# Relay_schematic.net
KiCad netlist of a schematic drawn in Altium Designer
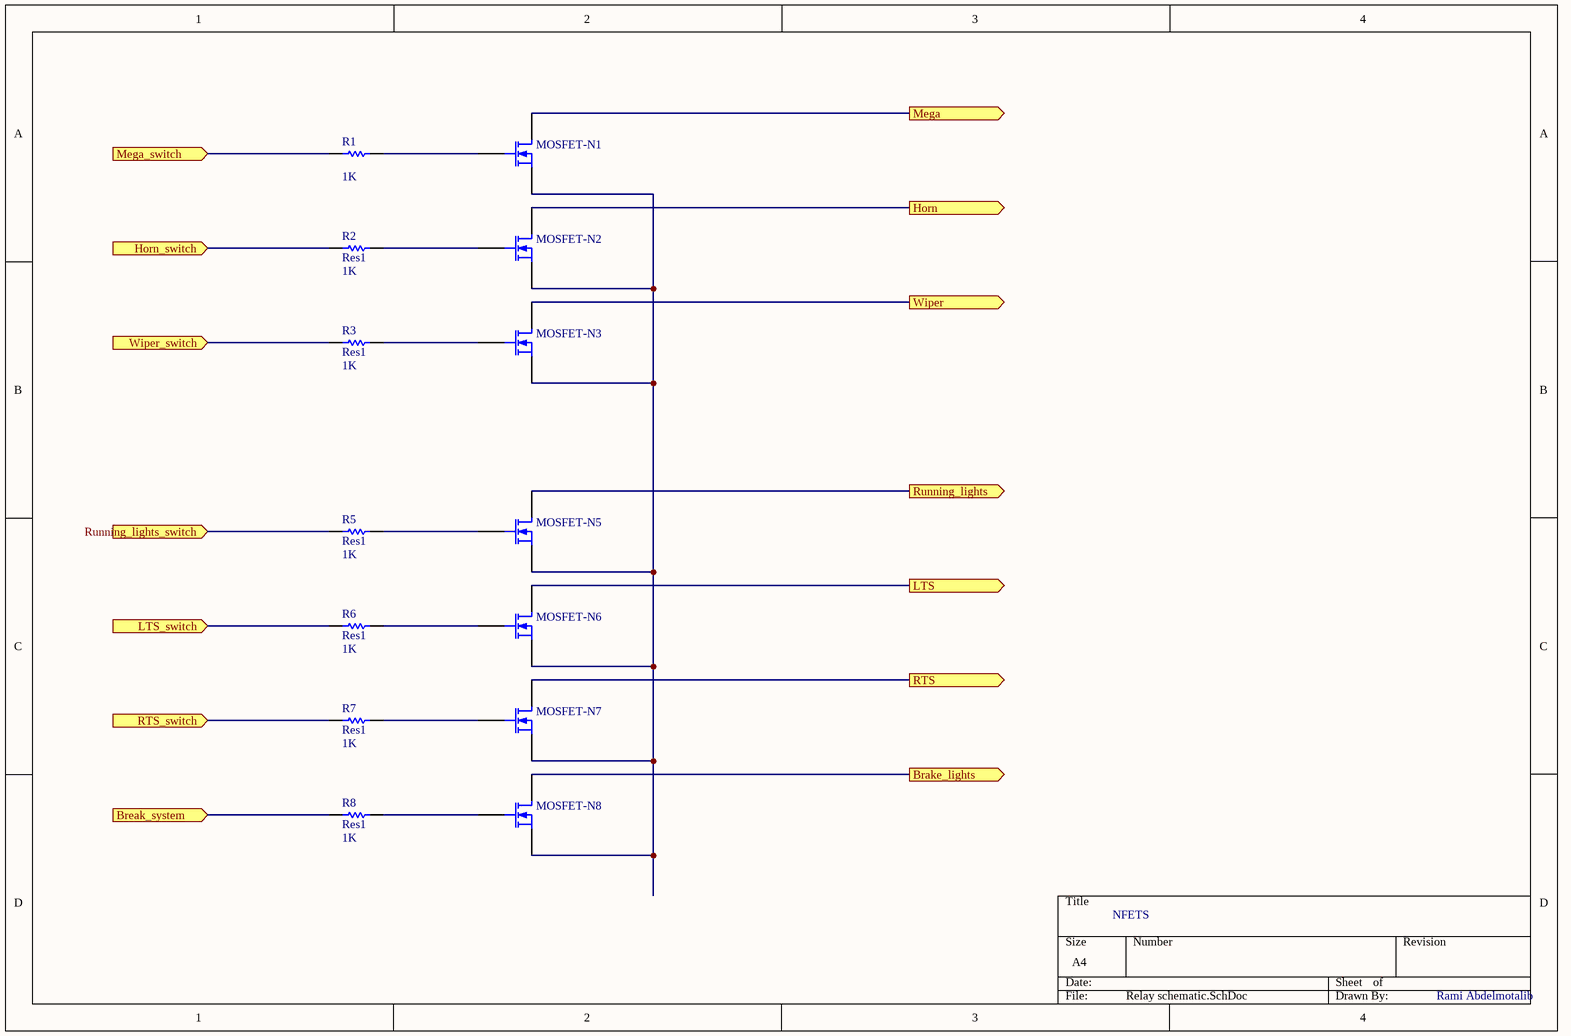
[diagram p0: Relay schematic.SchDoc]

(export (version "E")
  (design (tool "Eeschema 10.0.6"))
  (components
    (comp (ref "MOSFET-N1")
      (value "~")
      (footprint "E3")
      (description "N-Channel MOSFET")
      (fields (field (name "PUBLISHER") "Altium Limited"))
      (libsource (lib "Miscellaneous Devices") (part "MOSFET-N"))
    )
    (comp (ref "MOSFET-N2")
      (value "~")
      (footprint "E3")
      (description "N-Channel MOSFET")
      (fields (field (name "PUBLISHER") "Altium Limited"))
      (libsource (lib "Miscellaneous Devices") (part "MOSFET-N"))
    )
    (comp (ref "MOSFET-N3")
      (value "~")
      (footprint "E3")
      (description "N-Channel MOSFET")
      (fields (field (name "PUBLISHER") "Altium Limited"))
      (libsource (lib "Miscellaneous Devices") (part "MOSFET-N"))
    )
    (comp (ref "MOSFET-N5")
      (value "~")
      (footprint "E3")
      (description "N-Channel MOSFET")
      (fields (field (name "PUBLISHER") "Altium Limited"))
      (libsource (lib "Miscellaneous Devices") (part "MOSFET-N"))
    )
    (comp (ref "MOSFET-N6")
      (value "~")
      (footprint "E3")
      (description "N-Channel MOSFET")
      (fields (field (name "PUBLISHER") "Altium Limited"))
      (libsource (lib "Miscellaneous Devices") (part "MOSFET-N"))
    )
    (comp (ref "MOSFET-N7")
      (value "~")
      (footprint "E3")
      (description "N-Channel MOSFET")
      (fields (field (name "PUBLISHER") "Altium Limited"))
      (libsource (lib "Miscellaneous Devices") (part "MOSFET-N"))
    )
    (comp (ref "MOSFET-N8")
      (value "~")
      (footprint "E3")
      (description "N-Channel MOSFET")
      (fields (field (name "PUBLISHER") "Altium Limited"))
      (libsource (lib "Miscellaneous Devices") (part "MOSFET-N"))
    )
    (comp (ref "R1")
      (value "1K")
      (footprint "AXIAL-0.3")
      (description "Resistor")
      (fields (field (name "PUBLISHER") "Altium Limited"))
      (libsource (lib "Miscellaneous Devices") (part "Res1"))
    )
    (comp (ref "R2")
      (value "Res1")
      (footprint "AXIAL-0.3")
      (description "Resistor")
      (fields (field (name "ALTIUM_VALUE") "1K") (field (name "PUBLISHER") "Altium Limited"))
      (libsource (lib "Miscellaneous Devices") (part "Res1"))
    )
    (comp (ref "R3")
      (value "Res1")
      (footprint "AXIAL-0.3")
      (description "Resistor")
      (fields (field (name "ALTIUM_VALUE") "1K") (field (name "PUBLISHER") "Altium Limited"))
      (libsource (lib "Miscellaneous Devices") (part "Res1"))
    )
    (comp (ref "R5")
      (value "Res1")
      (footprint "AXIAL-0.3")
      (description "Resistor")
      (fields (field (name "ALTIUM_VALUE") "1K") (field (name "PUBLISHER") "Altium Limited"))
      (libsource (lib "Miscellaneous Devices") (part "Res1"))
    )
    (comp (ref "R6")
      (value "Res1")
      (footprint "AXIAL-0.3")
      (description "Resistor")
      (fields (field (name "ALTIUM_VALUE") "1K") (field (name "PUBLISHER") "Altium Limited"))
      (libsource (lib "Miscellaneous Devices") (part "Res1"))
    )
    (comp (ref "R7")
      (value "Res1")
      (footprint "AXIAL-0.3")
      (description "Resistor")
      (fields (field (name "ALTIUM_VALUE") "1K") (field (name "PUBLISHER") "Altium Limited"))
      (libsource (lib "Miscellaneous Devices") (part "Res1"))
    )
    (comp (ref "R8")
      (value "Res1")
      (footprint "AXIAL-0.3")
      (description "Resistor")
      (fields (field (name "ALTIUM_VALUE") "1K") (field (name "PUBLISHER") "Altium Limited"))
      (libsource (lib "Miscellaneous Devices") (part "Res1"))
    )
  )
  (nets
    (net (code "1") (name "/Brake_lights") (class "Default")
      (node (ref "MOSFET-N8") (pin "1") (pinfunction "D_1") (pintype "passive"))
    )
    (net (code "2") (name "/Break_system") (class "Default")
      (node (ref "R8") (pin "1") (pinfunction "1_1") (pintype "passive"))
    )
    (net (code "3") (name "/Horn") (class "Default")
      (node (ref "MOSFET-N2") (pin "1") (pinfunction "D_1") (pintype "passive"))
    )
    (net (code "4") (name "/Horn_switch") (class "Default")
      (node (ref "R2") (pin "1") (pinfunction "1_1") (pintype "passive"))
    )
    (net (code "5") (name "/LTS") (class "Default")
      (node (ref "MOSFET-N6") (pin "1") (pinfunction "D_1") (pintype "passive"))
    )
    (net (code "6") (name "/LTS_switch") (class "Default")
      (node (ref "R6") (pin "1") (pinfunction "1_1") (pintype "passive"))
    )
    (net (code "7") (name "/Mega") (class "Default")
      (node (ref "MOSFET-N1") (pin "1") (pinfunction "D_1") (pintype "passive"))
    )
    (net (code "8") (name "/Mega_switch") (class "Default")
      (node (ref "R1") (pin "1") (pinfunction "1_1") (pintype "passive"))
    )
    (net (code "9") (name "/RTS") (class "Default")
      (node (ref "MOSFET-N7") (pin "1") (pinfunction "D_1") (pintype "passive"))
    )
    (net (code "10") (name "/RTS_switch") (class "Default")
      (node (ref "R7") (pin "1") (pinfunction "1_1") (pintype "passive"))
    )
    (net (code "11") (name "/Running_lights") (class "Default")
      (node (ref "MOSFET-N5") (pin "1") (pinfunction "D_1") (pintype "passive"))
    )
    (net (code "12") (name "/Running_lights_switch") (class "Default")
      (node (ref "R5") (pin "1") (pinfunction "1_1") (pintype "passive"))
    )
    (net (code "13") (name "/Wiper") (class "Default")
      (node (ref "MOSFET-N3") (pin "1") (pinfunction "D_1") (pintype "passive"))
    )
    (net (code "14") (name "/Wiper_switch") (class "Default")
      (node (ref "R3") (pin "1") (pinfunction "1_1") (pintype "passive"))
    )
    (net (code "15") (name "Net-(MOSFET-N1-G)") (class "Default")
      (node (ref "MOSFET-N1") (pin "2") (pinfunction "G_2") (pintype "passive"))
      (node (ref "R1") (pin "2") (pinfunction "2_2") (pintype "passive"))
    )
    (net (code "16") (name "Net-(MOSFET-N1-S)") (class "Default")
      (node (ref "MOSFET-N1") (pin "3") (pinfunction "S_3") (pintype "passive"))
      (node (ref "MOSFET-N2") (pin "3") (pinfunction "S_3") (pintype "passive"))
      (node (ref "MOSFET-N3") (pin "3") (pinfunction "S_3") (pintype "passive"))
      (node (ref "MOSFET-N5") (pin "3") (pinfunction "S_3") (pintype "passive"))
      (node (ref "MOSFET-N6") (pin "3") (pinfunction "S_3") (pintype "passive"))
      (node (ref "MOSFET-N7") (pin "3") (pinfunction "S_3") (pintype "passive"))
      (node (ref "MOSFET-N8") (pin "3") (pinfunction "S_3") (pintype "passive"))
    )
    (net (code "17") (name "Net-(MOSFET-N2-G)") (class "Default")
      (node (ref "MOSFET-N2") (pin "2") (pinfunction "G_2") (pintype "passive"))
      (node (ref "R2") (pin "2") (pinfunction "2_2") (pintype "passive"))
    )
    (net (code "18") (name "Net-(MOSFET-N3-G)") (class "Default")
      (node (ref "MOSFET-N3") (pin "2") (pinfunction "G_2") (pintype "passive"))
      (node (ref "R3") (pin "2") (pinfunction "2_2") (pintype "passive"))
    )
    (net (code "19") (name "Net-(MOSFET-N5-G)") (class "Default")
      (node (ref "MOSFET-N5") (pin "2") (pinfunction "G_2") (pintype "passive"))
      (node (ref "R5") (pin "2") (pinfunction "2_2") (pintype "passive"))
    )
    (net (code "20") (name "Net-(MOSFET-N6-G)") (class "Default")
      (node (ref "MOSFET-N6") (pin "2") (pinfunction "G_2") (pintype "passive"))
      (node (ref "R6") (pin "2") (pinfunction "2_2") (pintype "passive"))
    )
    (net (code "21") (name "Net-(MOSFET-N7-G)") (class "Default")
      (node (ref "MOSFET-N7") (pin "2") (pinfunction "G_2") (pintype "passive"))
      (node (ref "R7") (pin "2") (pinfunction "2_2") (pintype "passive"))
    )
    (net (code "22") (name "Net-(MOSFET-N8-G)") (class "Default")
      (node (ref "MOSFET-N8") (pin "2") (pinfunction "G_2") (pintype "passive"))
      (node (ref "R8") (pin "2") (pinfunction "2_2") (pintype "passive"))
    )
  )
)
